# Nixie_4.net
KiCad netlist of a schematic drawn in Altium Designer
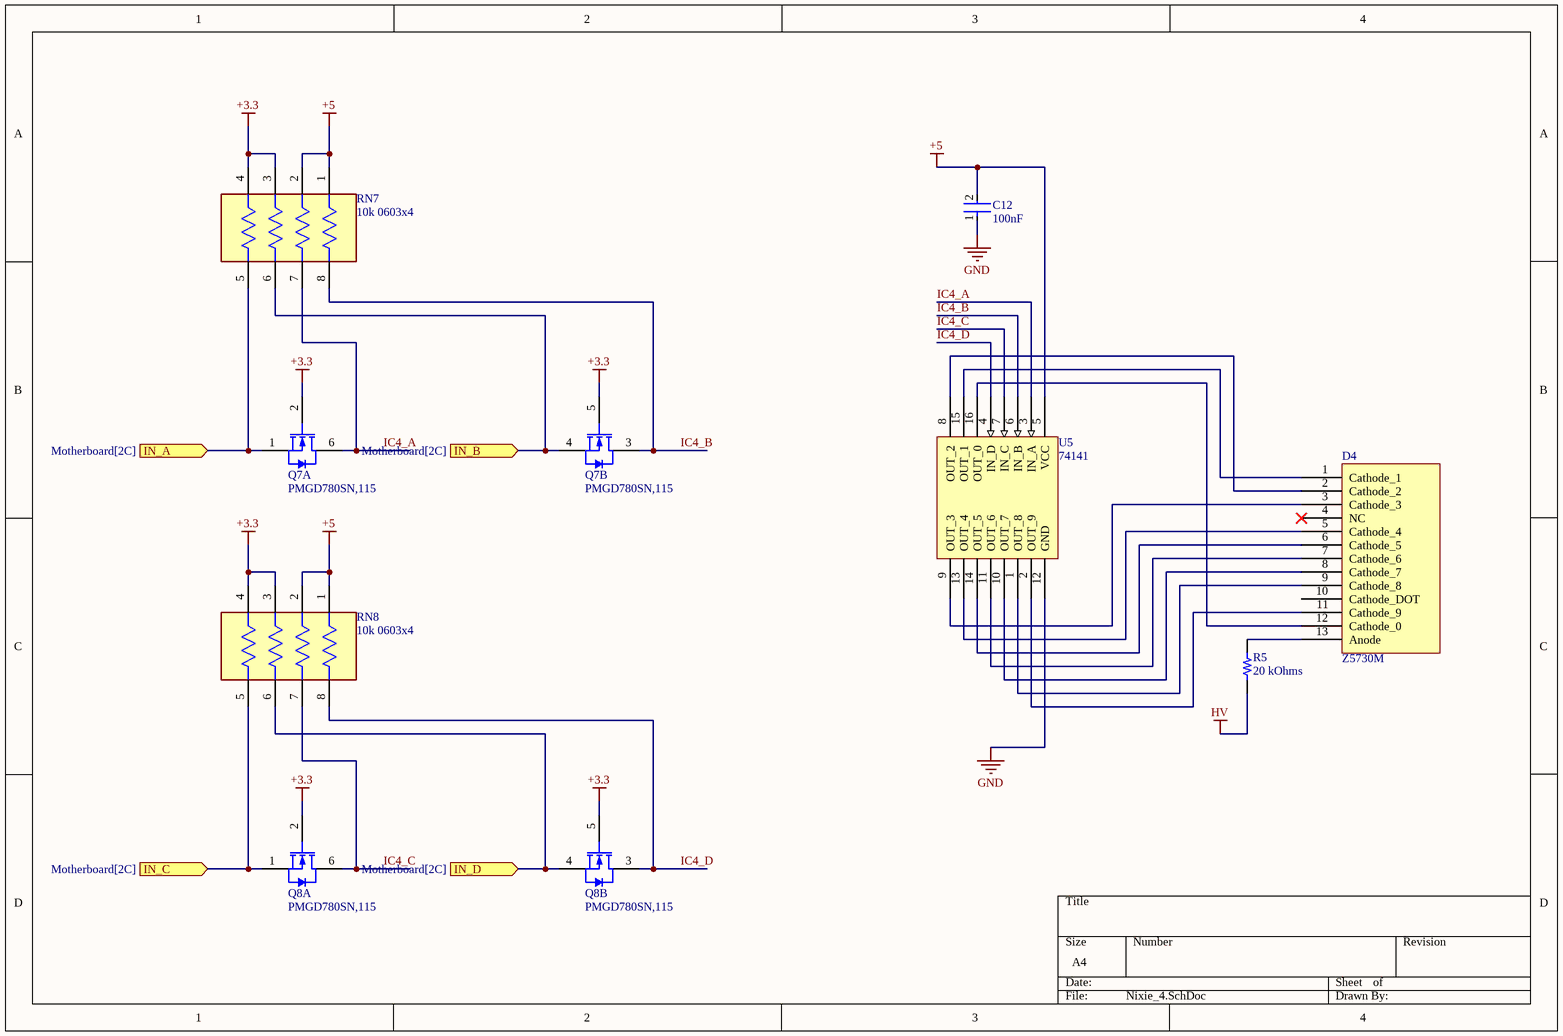
[diagram p0: Nixie_4.SchDoc]

(export (version "E")
  (design (tool "Eeschema 10.0.6"))
  (components
    (comp (ref "C12")
      (value "100nF")
      (footprint "FP-C1005-050-0_15-MFG")
      (description "CAP CER 100nF 10V X5R 0402")
      (fields (field (name "TOLERANCE") "20%") (field (name "VOLTAGE") "10V"))
      (libsource (lib "Altium Content Vault") (part "11868f565c42a9108669ba33697ecf6"))
    )
    (comp (ref "D4") (value "Z5730M") (footprint "Z5730M") (libsource (lib "Z5730M") (part "Z5730M")))
    (comp (ref "Q7")
      (value "PMGD780SN,115")
      (footprint "NXP-SOT363_N")
      (description "Dual N-Channel uTrenchMOS Standard Level FET, 60 V, 0.49 A, 6-Pin SOT363, Tape and Reel")
      (fields (field (name "MANUFACTURER") "NXP Semiconductors"))
      (libsource (lib "Altium Content Vault") (part "NXP-NNMOS-SGDSGD-6_B"))
    )
    (comp (ref "Q8")
      (value "PMGD780SN,115")
      (footprint "NXP-SOT363_N")
      (description "Dual N-Channel uTrenchMOS Standard Level FET, 60 V, 0.49 A, 6-Pin SOT363, Tape and Reel")
      (fields (field (name "MANUFACTURER") "NXP Semiconductors"))
      (libsource (lib "Altium Content Vault") (part "NXP-NNMOS-SGDSGD-6_B"))
    )
    (comp (ref "R5")
      (value "20 kOhms")
      (footprint "RES 1210_3225")
      (description "RES SMD 20K OHM 1% 3/4W 1210")
      (fields (field (name "PART NUMBER") "CRCW121020K0FKEAHP") (field (name "MANUFACTURER") "Vishay Dale"))
      (libsource (lib "Celestial Altium Library - altium_library") (part "Resistor"))
    )
    (comp (ref "RN7")
      (value "10k 0603x4")
      (footprint "FP-EXB38V-MFG")
      (description "RES ARRAY 4 RES 10K OHM 1206\r\nRC-ML08W103JT")
      (fields (field (name "TOLERANCE") "5%"))
      (libsource (lib "Altium Content Vault") (part "2ca08171d0bbdee8be62227dae509d7"))
    )
    (comp (ref "RN8")
      (value "10k 0603x4")
      (footprint "FP-EXB38V-MFG")
      (description "RES ARRAY 4 RES 10K OHM 1206\r\nRC-ML08W103JT")
      (fields (field (name "TOLERANCE") "5%"))
      (libsource (lib "Altium Content Vault") (part "2ca08171d0bbdee8be62227dae509d7"))
    )
    (comp (ref "U5") (value "74141") (footprint "DIP-16") (libsource (lib "Z5730M") (part "74141")))
  )
  (nets
    (net (code "1") (name "+3.3") (class "Default")
      (node (ref "Q7") (pin "2") (pinfunction "G1_2") (pintype "passive"))
      (node (ref "Q7") (pin "5") (pinfunction "G2_5") (pintype "passive"))
      (node (ref "Q8") (pin "2") (pinfunction "G1_2") (pintype "passive"))
      (node (ref "Q8") (pin "5") (pinfunction "G2_5") (pintype "passive"))
      (node (ref "RN7") (pin "3") (pinfunction "3_3") (pintype "passive"))
      (node (ref "RN7") (pin "4") (pinfunction "4_4") (pintype "passive"))
      (node (ref "RN8") (pin "3") (pinfunction "3_3") (pintype "passive"))
      (node (ref "RN8") (pin "4") (pinfunction "4_4") (pintype "passive"))
    )
    (net (code "2") (name "+5") (class "Default")
      (node (ref "C12") (pin "2") (pinfunction "2_2") (pintype "passive"))
      (node (ref "RN7") (pin "1") (pinfunction "1_1") (pintype "passive"))
      (node (ref "RN7") (pin "2") (pinfunction "2_2") (pintype "passive"))
      (node (ref "RN8") (pin "1") (pinfunction "1_1") (pintype "passive"))
      (node (ref "RN8") (pin "2") (pinfunction "2_2") (pintype "passive"))
      (node (ref "U5") (pin "5") (pinfunction "VCC_5") (pintype "power_in"))
    )
    (net (code "3") (name "/IC4_A") (class "Default")
      (node (ref "Q7") (pin "6") (pinfunction "D1_6") (pintype "passive"))
      (node (ref "RN7") (pin "7") (pinfunction "7_7") (pintype "passive"))
      (node (ref "U5") (pin "3") (pinfunction "IN_A_3") (pintype "input"))
    )
    (net (code "4") (name "/IC4_B") (class "Default")
      (node (ref "Q7") (pin "3") (pinfunction "D2_3") (pintype "passive"))
      (node (ref "RN7") (pin "8") (pinfunction "8_8") (pintype "passive"))
      (node (ref "U5") (pin "6") (pinfunction "IN_B_6") (pintype "input"))
    )
    (net (code "5") (name "/IC4_C") (class "Default")
      (node (ref "Q8") (pin "6") (pinfunction "D1_6") (pintype "passive"))
      (node (ref "RN8") (pin "7") (pinfunction "7_7") (pintype "passive"))
      (node (ref "U5") (pin "7") (pinfunction "IN_C_7") (pintype "input"))
    )
    (net (code "6") (name "/IC4_D") (class "Default")
      (node (ref "Q8") (pin "3") (pinfunction "D2_3") (pintype "passive"))
      (node (ref "RN8") (pin "8") (pinfunction "8_8") (pintype "passive"))
      (node (ref "U5") (pin "4") (pinfunction "IN_D_4") (pintype "input"))
    )
    (net (code "7") (name "/IN_A") (class "Default")
      (node (ref "Q7") (pin "1") (pinfunction "S1_1") (pintype "passive"))
      (node (ref "RN7") (pin "5") (pinfunction "5_5") (pintype "passive"))
    )
    (net (code "8") (name "/IN_B") (class "Default")
      (node (ref "Q7") (pin "4") (pinfunction "S2_4") (pintype "passive"))
      (node (ref "RN7") (pin "6") (pinfunction "6_6") (pintype "passive"))
    )
    (net (code "9") (name "/IN_C") (class "Default")
      (node (ref "Q8") (pin "1") (pinfunction "S1_1") (pintype "passive"))
      (node (ref "RN8") (pin "5") (pinfunction "5_5") (pintype "passive"))
    )
    (net (code "10") (name "/IN_D") (class "Default")
      (node (ref "Q8") (pin "4") (pinfunction "S2_4") (pintype "passive"))
      (node (ref "RN8") (pin "6") (pinfunction "6_6") (pintype "passive"))
    )
    (net (code "11") (name "GND") (class "Default")
      (node (ref "C12") (pin "1") (pinfunction "1_1") (pintype "passive"))
      (node (ref "U5") (pin "12") (pinfunction "GND_12") (pintype "power_in"))
    )
    (net (code "12") (name "HV") (class "Default")
      (node (ref "R5") (pin "1") (pinfunction "1_1") (pintype "passive"))
    )
    (net (code "13") (name "Net-(D4-Anode)") (class "Default")
      (node (ref "D4") (pin "13") (pinfunction "Anode_13") (pintype "passive"))
      (node (ref "R5") (pin "2") (pinfunction "2_2") (pintype "passive"))
    )
    (net (code "14") (name "Net-(D4-Cathode_0)") (class "Default")
      (node (ref "D4") (pin "12") (pinfunction "Cathode_0_12") (pintype "passive"))
      (node (ref "U5") (pin "16") (pinfunction "OUT_0_16") (pintype "open_collector"))
    )
    (net (code "15") (name "Net-(D4-Cathode_1)") (class "Default")
      (node (ref "D4") (pin "1") (pinfunction "Cathode_1_1") (pintype "passive"))
      (node (ref "U5") (pin "15") (pinfunction "OUT_1_15") (pintype "open_collector"))
    )
    (net (code "16") (name "Net-(D4-Cathode_2)") (class "Default")
      (node (ref "D4") (pin "2") (pinfunction "Cathode_2_2") (pintype "passive"))
      (node (ref "U5") (pin "8") (pinfunction "OUT_2_8") (pintype "open_collector"))
    )
    (net (code "17") (name "Net-(D4-Cathode_3)") (class "Default")
      (node (ref "D4") (pin "3") (pinfunction "Cathode_3_3") (pintype "passive"))
      (node (ref "U5") (pin "9") (pinfunction "OUT_3_9") (pintype "open_collector"))
    )
    (net (code "18") (name "Net-(D4-Cathode_4)") (class "Default")
      (node (ref "D4") (pin "5") (pinfunction "Cathode_4_5") (pintype "passive"))
      (node (ref "U5") (pin "13") (pinfunction "OUT_4_13") (pintype "open_collector"))
    )
    (net (code "19") (name "Net-(D4-Cathode_5)") (class "Default")
      (node (ref "D4") (pin "6") (pinfunction "Cathode_5_6") (pintype "passive"))
      (node (ref "U5") (pin "14") (pinfunction "OUT_5_14") (pintype "open_collector"))
    )
    (net (code "20") (name "Net-(D4-Cathode_6)") (class "Default")
      (node (ref "D4") (pin "7") (pinfunction "Cathode_6_7") (pintype "passive"))
      (node (ref "U5") (pin "11") (pinfunction "OUT_6_11") (pintype "open_collector"))
    )
    (net (code "21") (name "Net-(D4-Cathode_7)") (class "Default")
      (node (ref "D4") (pin "8") (pinfunction "Cathode_7_8") (pintype "passive"))
      (node (ref "U5") (pin "10") (pinfunction "OUT_7_10") (pintype "open_collector"))
    )
    (net (code "22") (name "Net-(D4-Cathode_8)") (class "Default")
      (node (ref "D4") (pin "9") (pinfunction "Cathode_8_9") (pintype "passive"))
      (node (ref "U5") (pin "1") (pinfunction "OUT_8_1") (pintype "open_collector"))
    )
    (net (code "23") (name "Net-(D4-Cathode_9)") (class "Default")
      (node (ref "D4") (pin "11") (pinfunction "Cathode_9_11") (pintype "passive"))
      (node (ref "U5") (pin "2") (pinfunction "OUT_9_2") (pintype "open_collector"))
    )
    (net (code "24") (name "unconnected-(D4-Cathode_DOT-Pad10)") (class "Default")
      (node (ref "D4") (pin "10") (pinfunction "Cathode_DOT_10") (pintype "passive"))
    )
    (net (code "25") (name "unconnected-(D4-NC-Pad4)") (class "Default")
      (node (ref "D4") (pin "4") (pinfunction "NC_4") (pintype "passive+no_connect"))
    )
  )
)
